# EXT_BLINKM.net
KiCad netlist of a schematic drawn in EAGLE
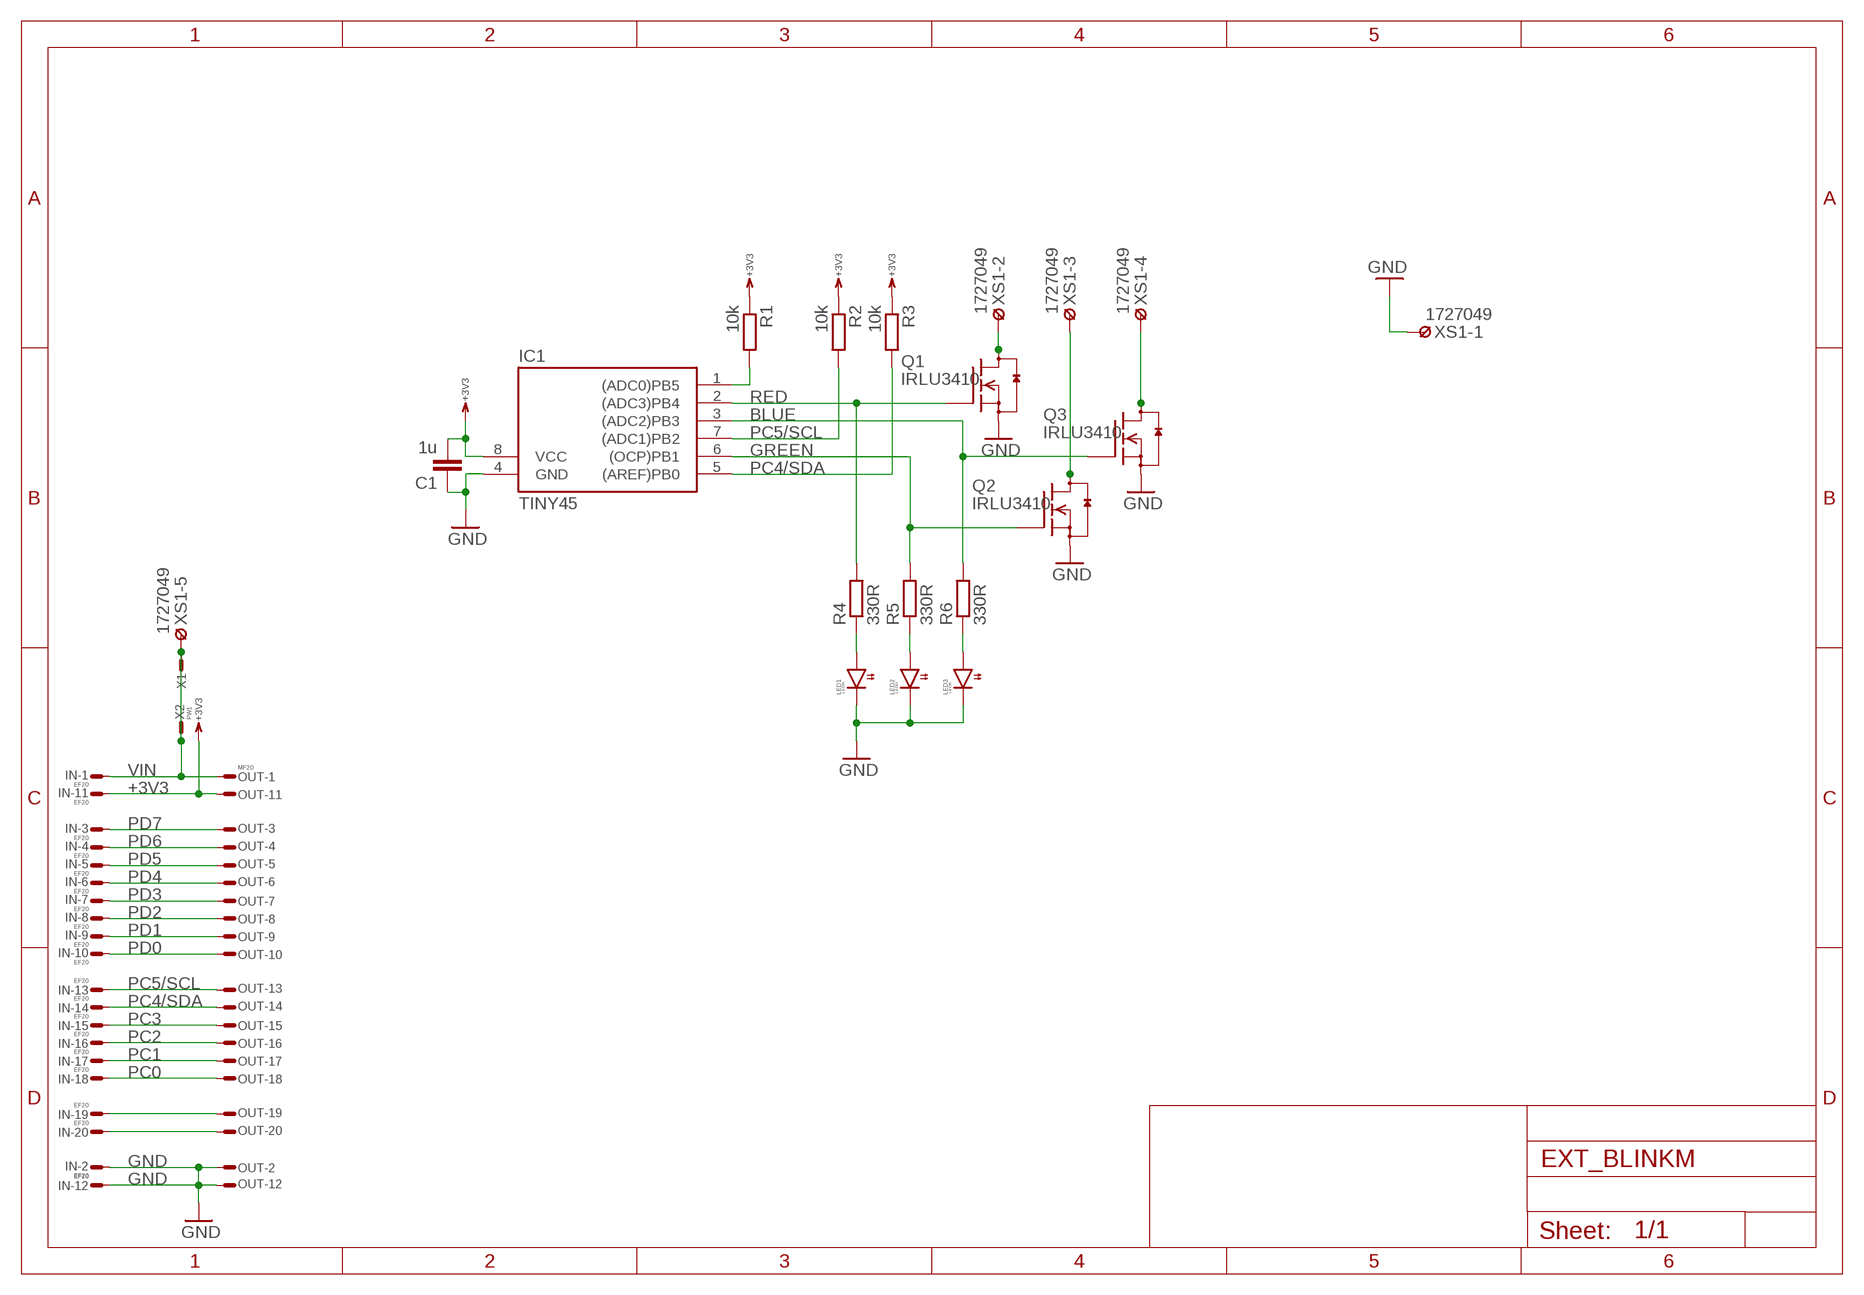
[diagram p0: schematic, sheet 1]

(export (version "E")
  (design (tool "Eeschema 10.0.6"))
  (components
    (comp (ref "C1")
      (value "1u")
      (footprint "eagle-import:0603")
      (libsource (lib "eagle-import") (part "C0603"))
    )
    (comp (ref "IC1")
      (value "TINY45")
      (footprint "eagle-import:SOIC8")
      (libsource (lib "eagle-import") (part "TINY15LS"))
    )
    (comp (ref "IN")
      (value "EF20")
      (footprint "eagle-import:FE10-2WS")
      (libsource (lib "eagle-import") (part "FE20ELS"))
    )
    (comp (ref "LED1")
      (value "LEDR")
      (footprint "eagle-import:1206")
      (libsource (lib "eagle-import") (part "LED1206"))
    )
    (comp (ref "LED2")
      (value "LEDG")
      (footprint "eagle-import:1206")
      (libsource (lib "eagle-import") (part "LED1206"))
    )
    (comp (ref "LED3")
      (value "LEDB")
      (footprint "eagle-import:1206")
      (libsource (lib "eagle-import") (part "LED1206"))
    )
    (comp (ref "OUT")
      (value "MF20")
      (footprint "eagle-import:ML20LS")
      (libsource (lib "eagle-import") (part "ML20?ELS"))
    )
    (comp (ref "Q1")
      (value "IRLU3410")
      (footprint "eagle-import:TO251AA")
      (libsource (lib "eagle-import") (part "FET-ND251"))
    )
    (comp (ref "Q2")
      (value "IRLU3410")
      (footprint "eagle-import:TO251AA")
      (libsource (lib "eagle-import") (part "FET-ND251"))
    )
    (comp (ref "Q3")
      (value "IRLU3410")
      (footprint "eagle-import:TO251AA")
      (libsource (lib "eagle-import") (part "FET-ND251"))
    )
    (comp (ref "R1")
      (value "10k")
      (footprint "eagle-import:0603")
      (libsource (lib "eagle-import") (part "R0603"))
    )
    (comp (ref "R2")
      (value "10k")
      (footprint "eagle-import:0603")
      (libsource (lib "eagle-import") (part "R0603"))
    )
    (comp (ref "R3")
      (value "10k")
      (footprint "eagle-import:0603")
      (libsource (lib "eagle-import") (part "R0603"))
    )
    (comp (ref "R4")
      (value "330R")
      (footprint "eagle-import:0603")
      (libsource (lib "eagle-import") (part "R0603"))
    )
    (comp (ref "R5")
      (value "330R")
      (footprint "eagle-import:0603")
      (libsource (lib "eagle-import") (part "R0603"))
    )
    (comp (ref "R6")
      (value "330R")
      (footprint "eagle-import:0603")
      (libsource (lib "eagle-import") (part "R0603"))
    )
    (comp (ref "X1")
      (value "WIREPADT1.6/0.9")
      (footprint "eagle-import:T1.6_0.9")
      (libsource (lib "eagle-import") (part "WIREPADT1.6/0.9"))
    )
    (comp (ref "X2")
      (value "PW1")
      (footprint "eagle-import:T1.6_0.9")
      (libsource (lib "eagle-import") (part "WIREPADT1.6/0.9"))
    )
    (comp (ref "XS1")
      (value "1727049")
      (footprint "eagle-import:1727049")
      (libsource (lib "eagle-import") (part "1727049"))
    )
  )
  (nets
    (net (code "1") (name "+3V3") (class "Default")
      (node (ref "C1") (pin "2") (pinfunction "2_2") (pintype "passive"))
      (node (ref "IC1") (pin "8") (pinfunction "VCC_8") (pintype "power_in"))
      (node (ref "IN") (pin "P$11") (pinfunction "S_P$11") (pintype "passive"))
      (node (ref "OUT") (pin "P$11") (pinfunction "S_P$11") (pintype "passive"))
      (node (ref "R1") (pin "1") (pinfunction "1_1") (pintype "passive"))
      (node (ref "R2") (pin "1") (pinfunction "1_1") (pintype "passive"))
      (node (ref "R3") (pin "1") (pinfunction "1_1") (pintype "passive"))
    )
    (net (code "2") (name "/BLUE") (class "Default")
      (node (ref "IC1") (pin "3") (pinfunction "(ADC2)PB3_3") (pintype "bidirectional"))
      (node (ref "Q3") (pin "1") (pinfunction "G_1") (pintype "passive"))
      (node (ref "R6") (pin "2") (pinfunction "2_2") (pintype "passive"))
    )
    (net (code "3") (name "/GREEN") (class "Default")
      (node (ref "IC1") (pin "6") (pinfunction "(OCP)PB1_6") (pintype "bidirectional"))
      (node (ref "Q2") (pin "1") (pinfunction "G_1") (pintype "passive"))
      (node (ref "R5") (pin "2") (pinfunction "2_2") (pintype "passive"))
    )
    (net (code "4") (name "/PC0") (class "Default")
      (node (ref "IN") (pin "P$18") (pinfunction "S_P$18") (pintype "passive"))
      (node (ref "OUT") (pin "P$18") (pinfunction "S_P$18") (pintype "passive"))
    )
    (net (code "5") (name "/PC1") (class "Default")
      (node (ref "IN") (pin "P$17") (pinfunction "S_P$17") (pintype "passive"))
      (node (ref "OUT") (pin "P$17") (pinfunction "S_P$17") (pintype "passive"))
    )
    (net (code "6") (name "/PC2") (class "Default")
      (node (ref "IN") (pin "P$16") (pinfunction "S_P$16") (pintype "passive"))
      (node (ref "OUT") (pin "P$16") (pinfunction "S_P$16") (pintype "passive"))
    )
    (net (code "7") (name "/PC3") (class "Default")
      (node (ref "IN") (pin "P$15") (pinfunction "S_P$15") (pintype "passive"))
      (node (ref "OUT") (pin "P$15") (pinfunction "S_P$15") (pintype "passive"))
    )
    (net (code "8") (name "/PC4{slash}SDA") (class "Default")
      (node (ref "IC1") (pin "5") (pinfunction "(AREF)PB0_5") (pintype "bidirectional"))
      (node (ref "IN") (pin "P$14") (pinfunction "S_P$14") (pintype "passive"))
      (node (ref "OUT") (pin "P$14") (pinfunction "S_P$14") (pintype "passive"))
      (node (ref "R3") (pin "2") (pinfunction "2_2") (pintype "passive"))
    )
    (net (code "9") (name "/PC5{slash}SCL") (class "Default")
      (node (ref "IC1") (pin "7") (pinfunction "(ADC1)PB2_7") (pintype "bidirectional"))
      (node (ref "IN") (pin "P$13") (pinfunction "S_P$13") (pintype "passive"))
      (node (ref "OUT") (pin "P$13") (pinfunction "S_P$13") (pintype "passive"))
      (node (ref "R2") (pin "2") (pinfunction "2_2") (pintype "passive"))
    )
    (net (code "10") (name "/PD0") (class "Default")
      (node (ref "IN") (pin "P$10") (pinfunction "S_P$10") (pintype "passive"))
      (node (ref "OUT") (pin "P$10") (pinfunction "S_P$10") (pintype "passive"))
    )
    (net (code "11") (name "/PD1") (class "Default")
      (node (ref "IN") (pin "P$9") (pinfunction "S_P$9") (pintype "passive"))
      (node (ref "OUT") (pin "P$9") (pinfunction "S_P$9") (pintype "passive"))
    )
    (net (code "12") (name "/PD2") (class "Default")
      (node (ref "IN") (pin "P$8") (pinfunction "S_P$8") (pintype "passive"))
      (node (ref "OUT") (pin "P$8") (pinfunction "S_P$8") (pintype "passive"))
    )
    (net (code "13") (name "/PD3") (class "Default")
      (node (ref "IN") (pin "P$7") (pinfunction "S_P$7") (pintype "passive"))
      (node (ref "OUT") (pin "P$7") (pinfunction "S_P$7") (pintype "passive"))
    )
    (net (code "14") (name "/PD4") (class "Default")
      (node (ref "IN") (pin "P$6") (pinfunction "S_P$6") (pintype "passive"))
      (node (ref "OUT") (pin "P$6") (pinfunction "S_P$6") (pintype "passive"))
    )
    (net (code "15") (name "/PD5") (class "Default")
      (node (ref "IN") (pin "P$5") (pinfunction "S_P$5") (pintype "passive"))
      (node (ref "OUT") (pin "P$5") (pinfunction "S_P$5") (pintype "passive"))
    )
    (net (code "16") (name "/PD6") (class "Default")
      (node (ref "IN") (pin "P$4") (pinfunction "S_P$4") (pintype "passive"))
      (node (ref "OUT") (pin "P$4") (pinfunction "S_P$4") (pintype "passive"))
    )
    (net (code "17") (name "/PD7") (class "Default")
      (node (ref "IN") (pin "P$3") (pinfunction "S_P$3") (pintype "passive"))
      (node (ref "OUT") (pin "P$3") (pinfunction "S_P$3") (pintype "passive"))
    )
    (net (code "18") (name "/RED") (class "Default")
      (node (ref "IC1") (pin "2") (pinfunction "(ADC3)PB4_2") (pintype "bidirectional"))
      (node (ref "Q1") (pin "1") (pinfunction "G_1") (pintype "passive"))
      (node (ref "R4") (pin "2") (pinfunction "2_2") (pintype "passive"))
    )
    (net (code "19") (name "/VIN") (class "Default")
      (node (ref "IN") (pin "P$1") (pinfunction "S_P$1") (pintype "passive"))
      (node (ref "OUT") (pin "P$1") (pinfunction "S_P$1") (pintype "passive"))
      (node (ref "X1") (pin "1") (pinfunction "S_1") (pintype "passive"))
      (node (ref "X2") (pin "1") (pinfunction "S_1") (pintype "passive"))
      (node (ref "XS1") (pin "5") (pinfunction "K_5") (pintype "passive"))
    )
    (net (code "20") (name "GND") (class "Default")
      (node (ref "C1") (pin "1") (pinfunction "1_1") (pintype "passive"))
      (node (ref "IC1") (pin "4") (pinfunction "GND_4") (pintype "power_in"))
      (node (ref "IN") (pin "P$12") (pinfunction "S_P$12") (pintype "passive"))
      (node (ref "IN") (pin "P$2") (pinfunction "S_P$2") (pintype "passive"))
      (node (ref "LED1") (pin "2") (pinfunction "C_2") (pintype "bidirectional"))
      (node (ref "LED2") (pin "2") (pinfunction "C_2") (pintype "bidirectional"))
      (node (ref "LED3") (pin "2") (pinfunction "C_2") (pintype "bidirectional"))
      (node (ref "OUT") (pin "P$12") (pinfunction "S_P$12") (pintype "passive"))
      (node (ref "OUT") (pin "P$2") (pinfunction "S_P$2") (pintype "passive"))
      (node (ref "Q1") (pin "3") (pinfunction "S_3") (pintype "passive"))
      (node (ref "Q2") (pin "3") (pinfunction "S_3") (pintype "passive"))
      (node (ref "Q3") (pin "3") (pinfunction "S_3") (pintype "passive"))
      (node (ref "XS1") (pin "1") (pinfunction "K_1") (pintype "passive"))
    )
    (net (code "21") (name "Net-(IC1-(ADC0)PB5)") (class "Default")
      (node (ref "IC1") (pin "1") (pinfunction "(ADC0)PB5_1") (pintype "bidirectional"))
      (node (ref "R1") (pin "2") (pinfunction "2_2") (pintype "passive"))
    )
    (net (code "22") (name "Net-(INK-S)") (class "Default")
      (node (ref "IN") (pin "P$19") (pinfunction "S_P$19") (pintype "passive"))
      (node (ref "OUT") (pin "P$19") (pinfunction "S_P$19") (pintype "passive"))
    )
    (net (code "23") (name "Net-(INM-S)") (class "Default")
      (node (ref "IN") (pin "P$20") (pinfunction "S_P$20") (pintype "passive"))
      (node (ref "OUT") (pin "P$20") (pinfunction "S_P$20") (pintype "passive"))
    )
    (net (code "24") (name "Net-(LED1-A)") (class "Default")
      (node (ref "LED1") (pin "1") (pinfunction "A_1") (pintype "bidirectional"))
      (node (ref "R4") (pin "1") (pinfunction "1_1") (pintype "passive"))
    )
    (net (code "25") (name "Net-(LED2-A)") (class "Default")
      (node (ref "LED2") (pin "1") (pinfunction "A_1") (pintype "bidirectional"))
      (node (ref "R5") (pin "1") (pinfunction "1_1") (pintype "passive"))
    )
    (net (code "26") (name "Net-(LED3-A)") (class "Default")
      (node (ref "LED3") (pin "1") (pinfunction "A_1") (pintype "bidirectional"))
      (node (ref "R6") (pin "1") (pinfunction "1_1") (pintype "passive"))
    )
    (net (code "27") (name "Net-(Q1-D)") (class "Default")
      (node (ref "Q1") (pin "2") (pinfunction "D_2") (pintype "passive"))
      (node (ref "XS1") (pin "2") (pinfunction "K_2") (pintype "passive"))
    )
    (net (code "28") (name "Net-(Q2-D)") (class "Default")
      (node (ref "Q2") (pin "2") (pinfunction "D_2") (pintype "passive"))
      (node (ref "XS1") (pin "3") (pinfunction "K_3") (pintype "passive"))
    )
    (net (code "29") (name "Net-(Q3-D)") (class "Default")
      (node (ref "Q3") (pin "2") (pinfunction "D_2") (pintype "passive"))
      (node (ref "XS1") (pin "4") (pinfunction "K_4") (pintype "passive"))
    )
  )
)
